# metoutelete.net
KiCad netlist of a schematic drawn in EasyEDA
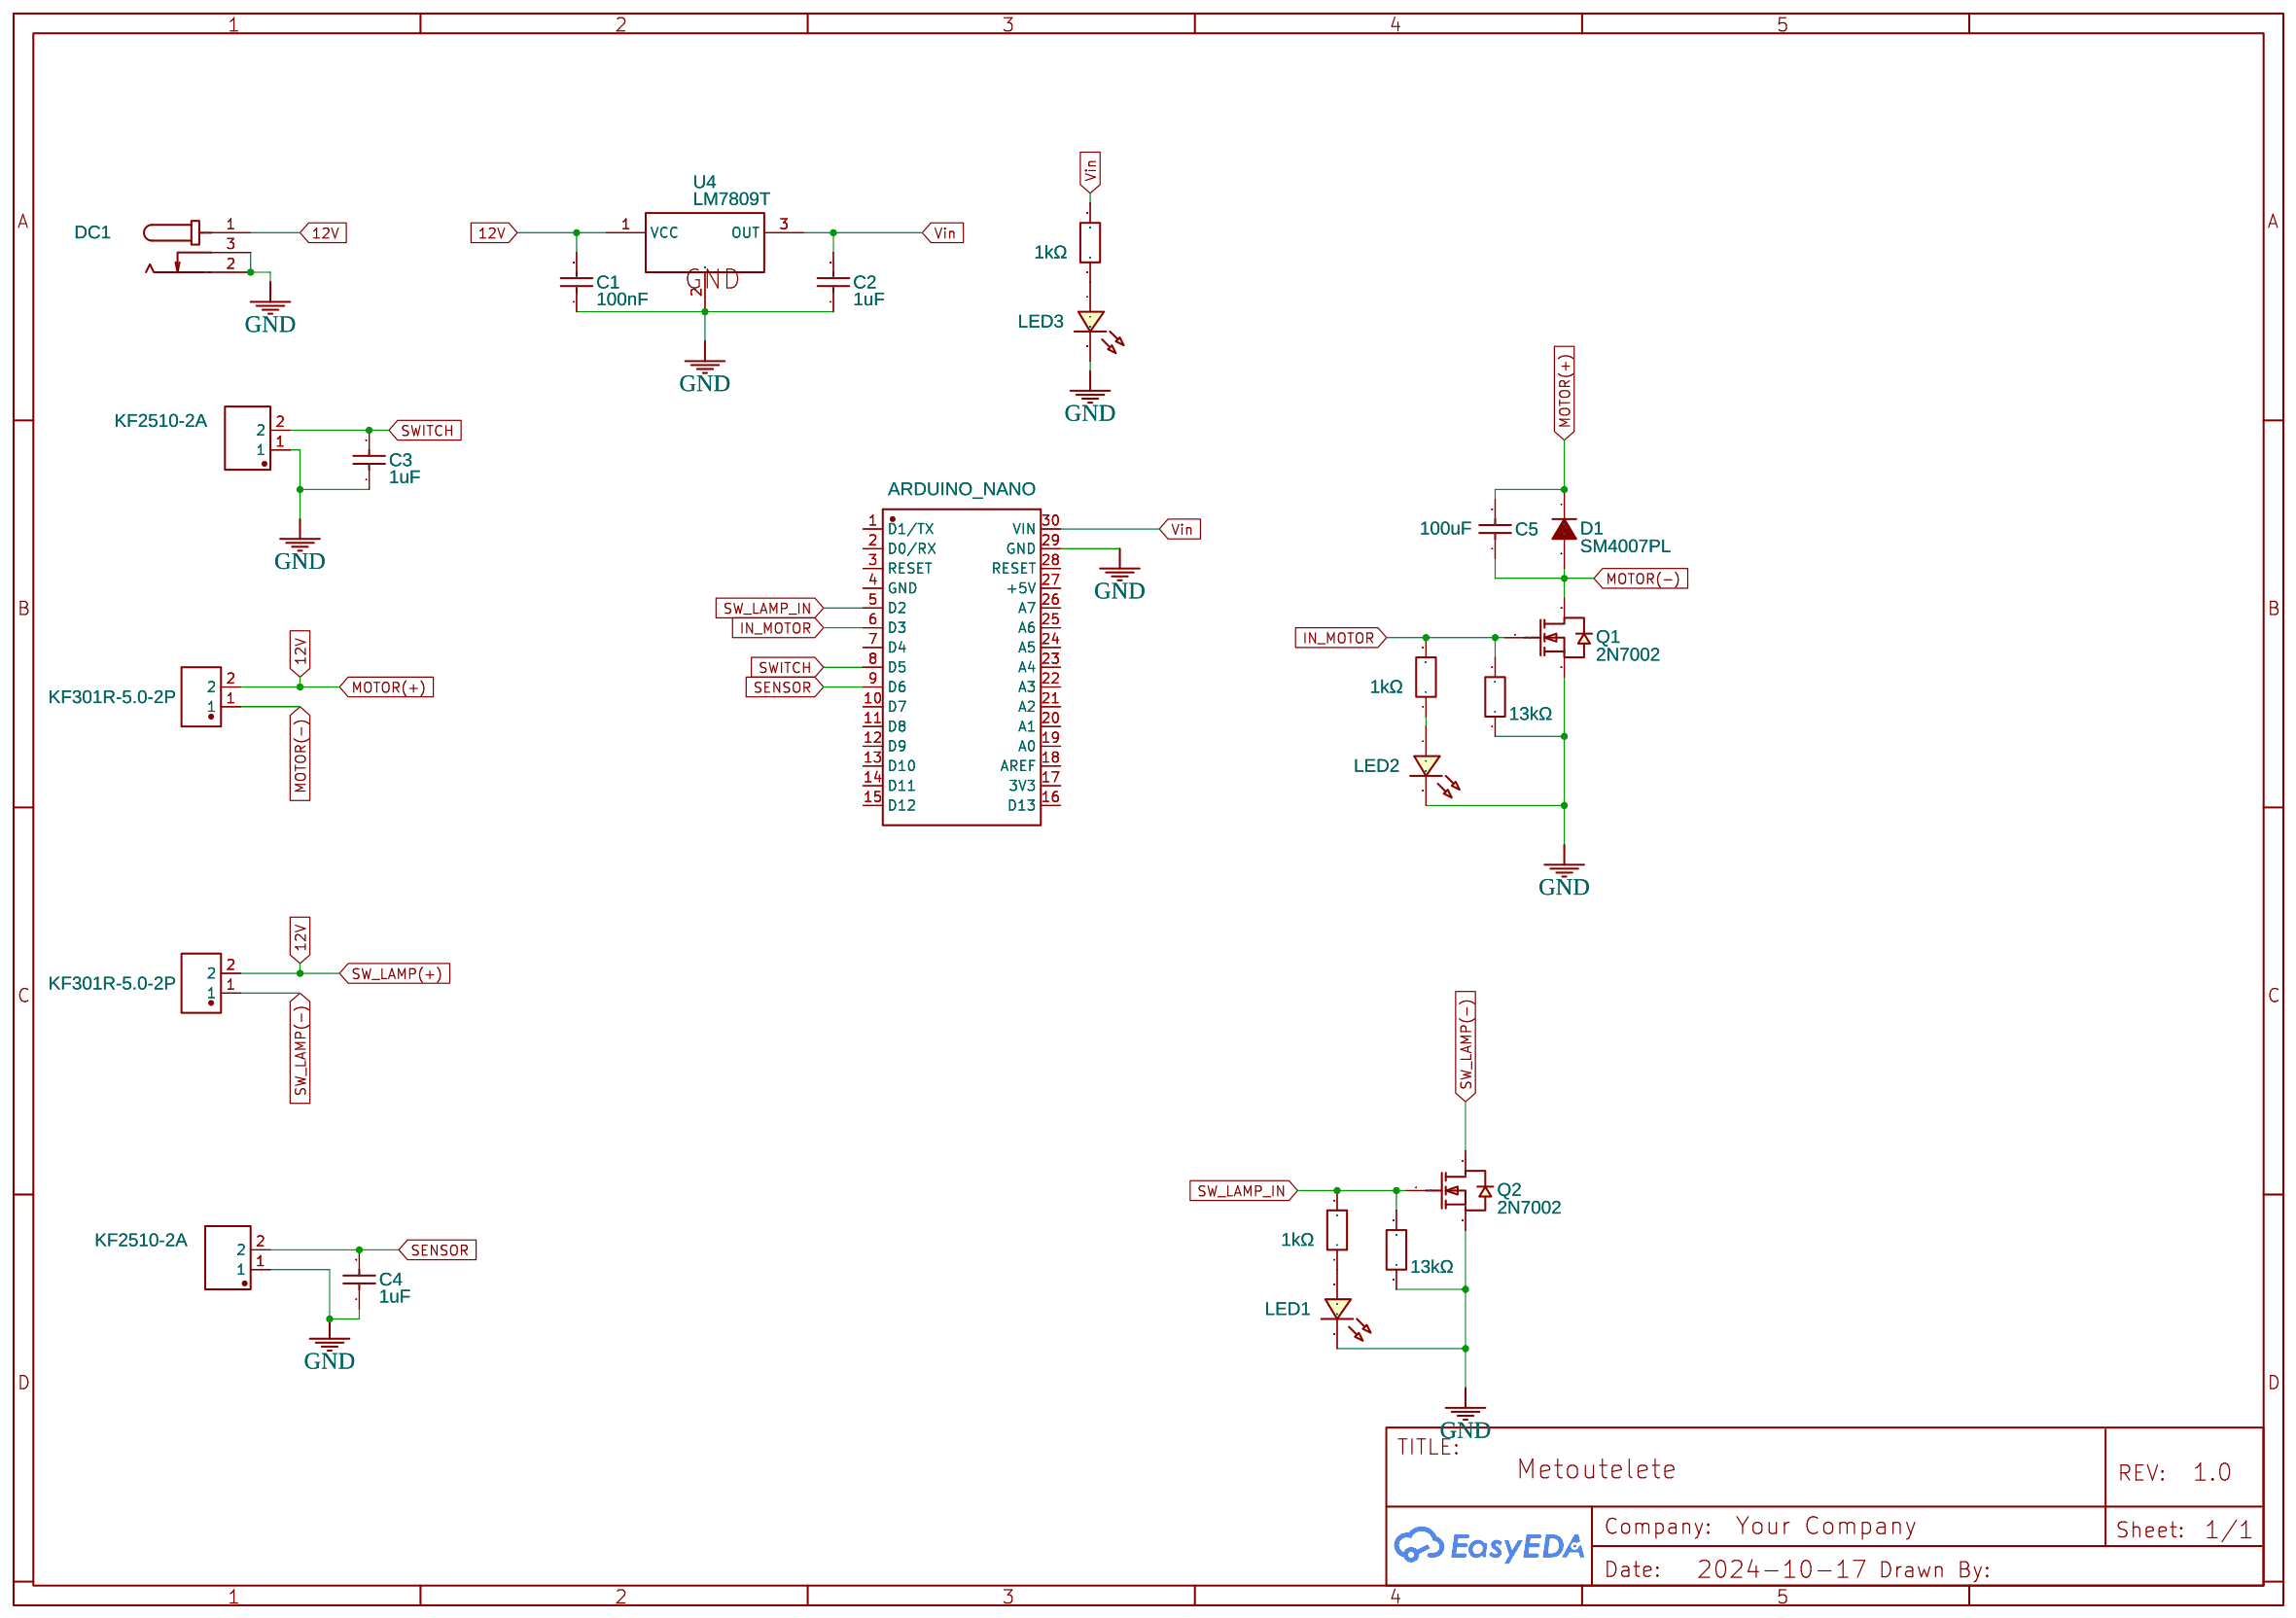
[diagram p0: schematic sheet]

(export (version "E")
  (design (tool "Eeschema 10.0.6"))
  (components
    (comp (ref "C1")
      (value "100nF")
      (fields (field (name "Manufacturer Part") "0201X104K6R3NT") (field (name "Manufacturer") "FH(风华)"))
      (libsource (lib "") (part "0201X104K6R3NT"))
    )
    (comp (ref "C2")
      (value "1uF")
      (fields (field (name "Manufacturer Part") "0603B474K500NT") (field (name "Manufacturer") "FH(风华)"))
      (libsource (lib "") (part "0603B474K500NT"))
    )
    (comp (ref "C3")
      (value "1uF")
      (fields (field (name "Manufacturer Part") "0603B474K500NT") (field (name "Manufacturer") "FH(风华)"))
      (libsource (lib "") (part "0603B474K500NT"))
    )
    (comp (ref "C4")
      (value "1uF")
      (fields (field (name "Manufacturer Part") "0603B474K500NT") (field (name "Manufacturer") "FH(风华)"))
      (libsource (lib "") (part "0603B474K500NT"))
    )
    (comp (ref "C5")
      (value "100uF")
      (fields (field (name "Manufacturer Part") "0201X104K6R3NT") (field (name "Manufacturer") "FH(风华)"))
      (libsource (lib "") (part "0201X104K6R3NT"))
    )
    (comp (ref "CN1")
      (value "KF2510-2A")
      (fields (field (name "Manufacturer Part") "2510-2A") (field (name "Manufacturer") "BOOMELE(博穆精密)"))
      (libsource (lib "") (part "KF2510-2A"))
    )
    (comp (ref "CN2")
      (value "KF2510-2A")
      (fields (field (name "Manufacturer Part") "2510-2A") (field (name "Manufacturer") "BOOMELE(博穆精密)"))
      (libsource (lib "") (part "KF2510-2A"))
    )
    (comp (ref "D1")
      (value "SM4007PL")
      (fields (field (name "Manufacturer") "MDD(辰达半导体)"))
      (libsource (lib "") (part "SM4007PL"))
    )
    (comp (ref "DC1")
      (value "DC-005-5A-2.0-SMT")
      (fields (field (name "Manufacturer") "XKB Connection(中国星坤)"))
      (libsource (lib "") (part "DC-005-5A-2.0-SMT"))
    )
    (comp (ref "LED1")
      (value "LED-0603_R")
      (fields
        (field (name "Manufacturer Part") "19-217/R6C-AL1M2VY/3T")
        (field (name "Manufacturer") "EVERLIGHT(台湾亿光)")
      )
      (libsource (lib "") (part "LED-0603_R"))
    )
    (comp (ref "LED2")
      (value "LED-0603_R")
      (fields
        (field (name "Manufacturer Part") "19-217/R6C-AL1M2VY/3T")
        (field (name "Manufacturer") "EVERLIGHT(台湾亿光)")
      )
      (libsource (lib "") (part "LED-0603_R"))
    )
    (comp (ref "LED3")
      (value "LED-0603_R")
      (fields
        (field (name "Manufacturer Part") "19-217/R6C-AL1M2VY/3T")
        (field (name "Manufacturer") "EVERLIGHT(台湾亿光)")
      )
      (libsource (lib "") (part "LED-0603_R"))
    )
    (comp (ref "Q1")
      (value "2N7002")
      (fields (field (name "Manufacturer") "CJ(江苏长电/长晶)"))
      (libsource (lib "") (part "2N7002"))
    )
    (comp (ref "Q2")
      (value "2N7002")
      (fields (field (name "Manufacturer") "CJ(江苏长电/长晶)"))
      (libsource (lib "") (part "2N7002"))
    )
    (comp (ref "U1") (value "ARDUINO_NANO") (libsource (lib "") (part "ARDUINO_NANO")))
    (comp (ref "U2")
      (value "13kΩ")
      (fields (field (name "Manufacturer Part") "0603 ±5% 10K") (field (name "Manufacturer") "VO(翔胜)"))
      (libsource (lib "") (part "0603 ±5% 10K"))
    )
    (comp (ref "U3")
      (value "13kΩ")
      (fields (field (name "Manufacturer Part") "0603 ±5% 10K") (field (name "Manufacturer") "VO(翔胜)"))
      (libsource (lib "") (part "0603 ±5% 10K"))
    )
    (comp (ref "U4")
      (value "LM7809T")
      (fields (field (name "Manufacturer") "HGSEMI(华冠)"))
      (libsource (lib "") (part "LM7809T"))
    )
    (comp (ref "U5")
      (value "KF301R-5.0-2P")
      (fields (field (name "Manufacturer") "KEFA(科发)"))
      (libsource (lib "") (part "KF301R-5.0-2P"))
    )
    (comp (ref "U6")
      (value "KF301R-5.0-2P")
      (fields (field (name "Manufacturer") "KEFA(科发)"))
      (libsource (lib "") (part "KF301R-5.0-2P"))
    )
    (comp (ref "U7")
      (value "1kΩ")
      (fields (field (name "Manufacturer Part") "0603 ±5% 10K") (field (name "Manufacturer") "VO(翔胜)"))
      (libsource (lib "") (part "0603 ±5% 10K"))
    )
    (comp (ref "U8")
      (value "1kΩ")
      (fields (field (name "Manufacturer Part") "0603 ±5% 10K") (field (name "Manufacturer") "VO(翔胜)"))
      (libsource (lib "") (part "0603 ±5% 10K"))
    )
    (comp (ref "U9")
      (value "1kΩ")
      (fields (field (name "Manufacturer Part") "0603 ±5% 10K") (field (name "Manufacturer") "VO(翔胜)"))
      (libsource (lib "") (part "0603 ±5% 10K"))
    )
  )
  (nets
    (net (code "1") (name "12V") (class "Default")
      (node (ref "C1") (pin "2") (pinfunction "2_2") (pintype "input"))
      (node (ref "C5") (pin "2") (pinfunction "2_2") (pintype "input"))
      (node (ref "D1") (pin "1") (pinfunction "C_1") (pintype "unspecified"))
      (node (ref "DC1") (pin "1") (pinfunction "1_1") (pintype "unspecified"))
      (node (ref "U4") (pin "1") (pinfunction "VCC_1") (pintype "passive"))
      (node (ref "U5") (pin "2") (pinfunction "2_2") (pintype "unspecified"))
      (node (ref "U6") (pin "2") (pinfunction "2_2") (pintype "unspecified"))
    )
    (net (code "2") (name "GND") (class "Default")
      (node (ref "C1") (pin "1") (pinfunction "1_1") (pintype "input"))
      (node (ref "C2") (pin "1") (pinfunction "1_1") (pintype "input"))
      (node (ref "C3") (pin "1") (pinfunction "1_1") (pintype "input"))
      (node (ref "C4") (pin "1") (pinfunction "1_1") (pintype "input"))
      (node (ref "CN1") (pin "1") (pinfunction "1_1") (pintype "unspecified"))
      (node (ref "CN2") (pin "1") (pinfunction "1_1") (pintype "unspecified"))
      (node (ref "DC1") (pin "2") (pinfunction "2_2") (pintype "unspecified"))
      (node (ref "DC1") (pin "3") (pinfunction "3_3") (pintype "unspecified"))
      (node (ref "LED1") (pin "2") (pinfunction "2_2") (pintype "unspecified"))
      (node (ref "LED2") (pin "2") (pinfunction "2_2") (pintype "unspecified"))
      (node (ref "LED3") (pin "2") (pinfunction "2_2") (pintype "unspecified"))
      (node (ref "Q1") (pin "2") (pinfunction "S_2") (pintype "unspecified"))
      (node (ref "Q2") (pin "2") (pinfunction "S_2") (pintype "unspecified"))
      (node (ref "U1") (pin "29") (pinfunction "GND_29") (pintype "unspecified"))
      (node (ref "U2") (pin "1") (pinfunction "1_1") (pintype "unspecified"))
      (node (ref "U3") (pin "1") (pinfunction "1_1") (pintype "unspecified"))
      (node (ref "U4") (pin "2") (pinfunction "GND_2") (pintype "passive"))
    )
    (net (code "3") (name "IN_MOTOR") (class "Default")
      (node (ref "Q1") (pin "1") (pinfunction "G_1") (pintype "unspecified"))
      (node (ref "U1") (pin "6") (pinfunction "D3_6") (pintype "unspecified"))
      (node (ref "U3") (pin "2") (pinfunction "2_2") (pintype "unspecified"))
      (node (ref "U8") (pin "2") (pinfunction "2_2") (pintype "unspecified"))
    )
    (net (code "4") (name "MOTOR(-)") (class "Default")
      (node (ref "C5") (pin "1") (pinfunction "1_1") (pintype "input"))
      (node (ref "D1") (pin "2") (pinfunction "A_2") (pintype "unspecified"))
      (node (ref "Q1") (pin "3") (pinfunction "D_3") (pintype "unspecified"))
      (node (ref "U5") (pin "1") (pinfunction "1_1") (pintype "unspecified"))
    )
    (net (code "5") (name "Net-(LED1-Pad1)") (class "Default")
      (node (ref "LED1") (pin "1") (pinfunction "1_1") (pintype "unspecified"))
      (node (ref "U7") (pin "1") (pinfunction "1_1") (pintype "unspecified"))
    )
    (net (code "6") (name "Net-(LED2-Pad1)") (class "Default")
      (node (ref "LED2") (pin "1") (pinfunction "1_1") (pintype "unspecified"))
      (node (ref "U8") (pin "1") (pinfunction "1_1") (pintype "unspecified"))
    )
    (net (code "7") (name "Net-(LED3-Pad1)") (class "Default")
      (node (ref "LED3") (pin "1") (pinfunction "1_1") (pintype "unspecified"))
      (node (ref "U9") (pin "1") (pinfunction "1_1") (pintype "unspecified"))
    )
    (net (code "8") (name "SENSOR") (class "Default")
      (node (ref "C4") (pin "2") (pinfunction "2_2") (pintype "input"))
      (node (ref "CN2") (pin "2") (pinfunction "2_2") (pintype "unspecified"))
      (node (ref "U1") (pin "9") (pinfunction "D6_9") (pintype "unspecified"))
    )
    (net (code "9") (name "SWITCH") (class "Default")
      (node (ref "C3") (pin "2") (pinfunction "2_2") (pintype "input"))
      (node (ref "CN1") (pin "2") (pinfunction "2_2") (pintype "unspecified"))
      (node (ref "U1") (pin "8") (pinfunction "D5_8") (pintype "unspecified"))
    )
    (net (code "10") (name "SW_LAMP(-)") (class "Default")
      (node (ref "Q2") (pin "3") (pinfunction "D_3") (pintype "unspecified"))
      (node (ref "U6") (pin "1") (pinfunction "1_1") (pintype "unspecified"))
    )
    (net (code "11") (name "SW_LAMP_IN") (class "Default")
      (node (ref "Q2") (pin "1") (pinfunction "G_1") (pintype "unspecified"))
      (node (ref "U1") (pin "5") (pinfunction "D2_5") (pintype "unspecified"))
      (node (ref "U2") (pin "2") (pinfunction "2_2") (pintype "unspecified"))
      (node (ref "U7") (pin "2") (pinfunction "2_2") (pintype "unspecified"))
    )
    (net (code "12") (name "Vin") (class "Default")
      (node (ref "C2") (pin "2") (pinfunction "2_2") (pintype "input"))
      (node (ref "U1") (pin "30") (pinfunction "VIN_30") (pintype "unspecified"))
      (node (ref "U4") (pin "3") (pinfunction "OUT_3") (pintype "passive"))
      (node (ref "U9") (pin "2") (pinfunction "2_2") (pintype "unspecified"))
    )
    (net (code "13") (name "unconnected-(U1-+5V-Pad27)") (class "Default")
      (node (ref "U1") (pin "27") (pinfunction "+5V_27") (pintype "unspecified"))
    )
    (net (code "14") (name "unconnected-(U1-3V3-Pad17)") (class "Default")
      (node (ref "U1") (pin "17") (pinfunction "3V3_17") (pintype "unspecified"))
    )
    (net (code "15") (name "unconnected-(U1-A0-Pad19)") (class "Default")
      (node (ref "U1") (pin "19") (pinfunction "A0_19") (pintype "unspecified"))
    )
    (net (code "16") (name "unconnected-(U1-A1-Pad20)") (class "Default")
      (node (ref "U1") (pin "20") (pinfunction "A1_20") (pintype "unspecified"))
    )
    (net (code "17") (name "unconnected-(U1-A2-Pad21)") (class "Default")
      (node (ref "U1") (pin "21") (pinfunction "A2_21") (pintype "unspecified"))
    )
    (net (code "18") (name "unconnected-(U1-A3-Pad22)") (class "Default")
      (node (ref "U1") (pin "22") (pinfunction "A3_22") (pintype "unspecified"))
    )
    (net (code "19") (name "unconnected-(U1-A4-Pad23)") (class "Default")
      (node (ref "U1") (pin "23") (pinfunction "A4_23") (pintype "unspecified"))
    )
    (net (code "20") (name "unconnected-(U1-A5-Pad24)") (class "Default")
      (node (ref "U1") (pin "24") (pinfunction "A5_24") (pintype "unspecified"))
    )
    (net (code "21") (name "unconnected-(U1-A6-Pad25)") (class "Default")
      (node (ref "U1") (pin "25") (pinfunction "A6_25") (pintype "unspecified"))
    )
    (net (code "22") (name "unconnected-(U1-A7-Pad26)") (class "Default")
      (node (ref "U1") (pin "26") (pinfunction "A7_26") (pintype "unspecified"))
    )
    (net (code "23") (name "unconnected-(U1-AREF-Pad18)") (class "Default")
      (node (ref "U1") (pin "18") (pinfunction "AREF_18") (pintype "unspecified"))
    )
    (net (code "24") (name "unconnected-(U1-D0{slash}RX-Pad2)") (class "Default")
      (node (ref "U1") (pin "2") (pinfunction "D0/RX_2") (pintype "unspecified"))
    )
    (net (code "25") (name "unconnected-(U1-D1{slash}TX-Pad1)") (class "Default")
      (node (ref "U1") (pin "1") (pinfunction "D1/TX_1") (pintype "unspecified"))
    )
    (net (code "26") (name "unconnected-(U1-D4-Pad7)") (class "Default")
      (node (ref "U1") (pin "7") (pinfunction "D4_7") (pintype "unspecified"))
    )
    (net (code "27") (name "unconnected-(U1-D7-Pad10)") (class "Default")
      (node (ref "U1") (pin "10") (pinfunction "D7_10") (pintype "unspecified"))
    )
    (net (code "28") (name "unconnected-(U1-D8-Pad11)") (class "Default")
      (node (ref "U1") (pin "11") (pinfunction "D8_11") (pintype "unspecified"))
    )
    (net (code "29") (name "unconnected-(U1-D9-Pad12)") (class "Default")
      (node (ref "U1") (pin "12") (pinfunction "D9_12") (pintype "unspecified"))
    )
    (net (code "30") (name "unconnected-(U1-D10-Pad13)") (class "Default")
      (node (ref "U1") (pin "13") (pinfunction "D10_13") (pintype "unspecified"))
    )
    (net (code "31") (name "unconnected-(U1-D11-Pad14)") (class "Default")
      (node (ref "U1") (pin "14") (pinfunction "D11_14") (pintype "unspecified"))
    )
    (net (code "32") (name "unconnected-(U1-D12-Pad15)") (class "Default")
      (node (ref "U1") (pin "15") (pinfunction "D12_15") (pintype "unspecified"))
    )
    (net (code "33") (name "unconnected-(U1-D13-Pad16)") (class "Default")
      (node (ref "U1") (pin "16") (pinfunction "D13_16") (pintype "unspecified"))
    )
    (net (code "34") (name "unconnected-(U1-GND-Pad4)") (class "Default")
      (node (ref "U1") (pin "4") (pinfunction "GND_4") (pintype "unspecified"))
    )
    (net (code "35") (name "unconnected-(U1-RESET-Pad3)") (class "Default")
      (node (ref "U1") (pin "3") (pinfunction "RESET_3") (pintype "unspecified"))
    )
    (net (code "36") (name "unconnected-(U1-RESET-Pad28)") (class "Default")
      (node (ref "U1") (pin "28") (pinfunction "RESET_28") (pintype "unspecified"))
    )
  )
)
